# Sheet1.net
KiCad netlist of a schematic drawn in Altium Designer
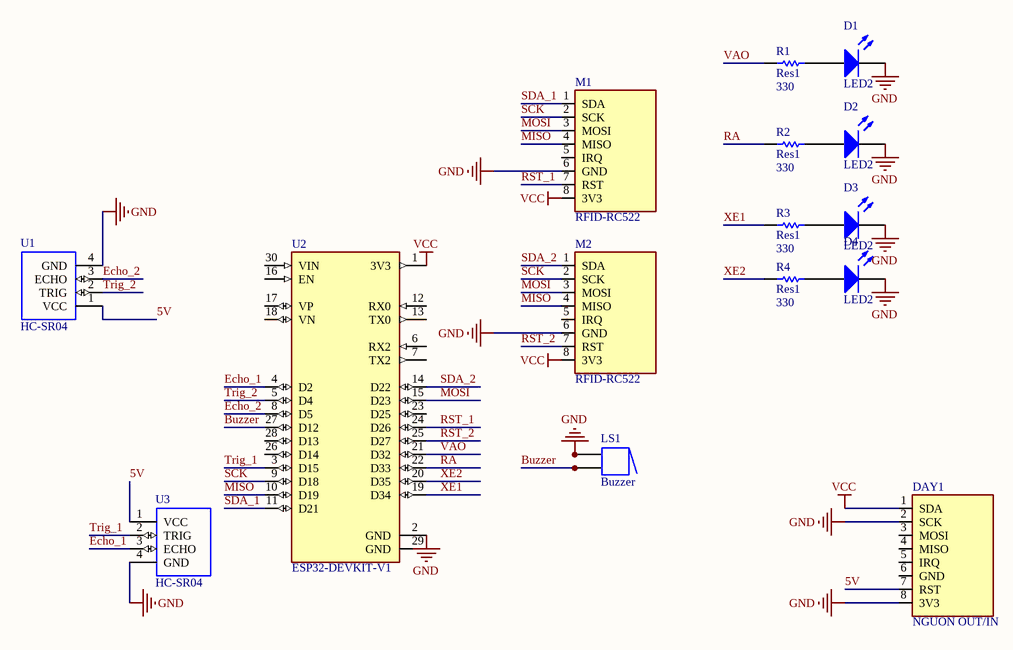
[diagram p0: Sheet1.SchDoc]

(export (version "E")
  (design (tool "Eeschema 10.0.6"))
  (components
    (comp (ref "D1")
      (value "LED2")
      (footprint "3.2X1.6X1.1")
      (description "Typical RED, GREEN, YELLOW, AMBER GaAs LED")
      (fields (field (name "PUBLISHER") "Altium Limited"))
      (libsource (lib "Miscellaneous Devices") (part "LED2"))
    )
    (comp (ref "D2")
      (value "LED2")
      (footprint "3.2X1.6X1.1")
      (description "Typical RED, GREEN, YELLOW, AMBER GaAs LED")
      (fields (field (name "PUBLISHER") "Altium Limited"))
      (libsource (lib "Miscellaneous Devices") (part "LED2"))
    )
    (comp (ref "D3")
      (value "LED2")
      (footprint "3.2X1.6X1.1")
      (description "Typical RED, GREEN, YELLOW, AMBER GaAs LED")
      (fields (field (name "PUBLISHER") "Altium Limited"))
      (libsource (lib "Miscellaneous Devices") (part "LED2"))
    )
    (comp (ref "D4")
      (value "LED2")
      (footprint "3.2X1.6X1.1")
      (description "Typical RED, GREEN, YELLOW, AMBER GaAs LED")
      (fields (field (name "PUBLISHER") "Altium Limited"))
      (libsource (lib "Miscellaneous Devices") (part "LED2"))
    )
    (comp (ref "DAY1")
      (value "NGUON OUT/IN")
      (footprint "RFID-RC522")
      (fields (field (name "MF") "Handson Technology") (field (name "MP") "RFID-RC522"))
      (libsource (lib "RFID-RC522") (part "RFID-RC522"))
    )
    (comp (ref "LS1")
      (value "Buzzer")
      (footprint "ABSM-1574")
      (description "Magnetic Transducer Buzzer")
      (fields (field (name "PUBLISHER") "Altium Limited"))
      (libsource (lib "Miscellaneous Devices") (part "Buzzer"))
    )
    (comp (ref "M1")
      (value "RFID-RC522")
      (footprint "RFID-RC522")
      (fields (field (name "MF") "Handson Technology"))
      (libsource (lib "RFID-RC522") (part "RFID-RC522"))
    )
    (comp (ref "M2")
      (value "RFID-RC522")
      (footprint "RFID-RC522")
      (fields (field (name "MF") "Handson Technology"))
      (libsource (lib "RFID-RC522") (part "RFID-RC522"))
    )
    (comp (ref "R1")
      (value "Res1")
      (footprint "AXIAL-0.3")
      (description "Resistor")
      (fields (field (name "ALTIUM_VALUE") "330") (field (name "PUBLISHER") "Altium Limited"))
      (libsource (lib "Miscellaneous Devices") (part "Res1"))
    )
    (comp (ref "R2")
      (value "Res1")
      (footprint "AXIAL-0.3")
      (description "Resistor")
      (fields (field (name "ALTIUM_VALUE") "330") (field (name "PUBLISHER") "Altium Limited"))
      (libsource (lib "Miscellaneous Devices") (part "Res1"))
    )
    (comp (ref "R3")
      (value "Res1")
      (footprint "AXIAL-0.3")
      (description "Resistor")
      (fields (field (name "ALTIUM_VALUE") "330") (field (name "PUBLISHER") "Altium Limited"))
      (libsource (lib "Miscellaneous Devices") (part "Res1"))
    )
    (comp (ref "R4")
      (value "Res1")
      (footprint "AXIAL-0.3")
      (description "Resistor")
      (fields (field (name "ALTIUM_VALUE") "330") (field (name "PUBLISHER") "Altium Limited"))
      (libsource (lib "Miscellaneous Devices") (part "Res1"))
    )
    (comp (ref "U1")
      (value "HC-SR04")
      (footprint "XCVR_HC-SR04")
      (description "Ultrasonic Sensor Module")
      (libsource (lib "HC-SR04") (part "HC-SR04"))
    )
    (comp (ref "U2")
      (value "ESP32-DEVKIT-V1")
      (footprint "MODULE_ESP32_DEVKIT_V1")
      (fields (field (name "MF") "Do it"))
      (libsource (lib "ESP32-DEVKIT-V1") (part "ESP32-DEVKIT-V1"))
    )
    (comp (ref "U3")
      (value "HC-SR04")
      (footprint "XCVR_HC-SR04")
      (description "Ultrasonic Sensor Module")
      (libsource (lib "HC-SR04") (part "HC-SR04"))
    )
  )
  (nets
    (net (code "1") (name "/5V") (class "Default")
      (node (ref "DAY1") (pin "7") (pinfunction "RST_7") (pintype "bidirectional"))
      (node (ref "U1") (pin "1") (pinfunction "VCC_1") (pintype "power_in"))
      (node (ref "U3") (pin "1") (pinfunction "VCC_1") (pintype "power_in"))
    )
    (net (code "2") (name "/Buzzer") (class "Default")
      (node (ref "LS1") (pin "2") (pinfunction "2_2") (pintype "passive"))
      (node (ref "LS1") (pin "2A") (pinfunction "2A_2A") (pintype "passive"))
      (node (ref "U2") (pin "27") (pinfunction "D12_27") (pintype "bidirectional"))
    )
    (net (code "3") (name "/Echo_1") (class "Default")
      (node (ref "U2") (pin "4") (pinfunction "D2_4") (pintype "bidirectional"))
      (node (ref "U3") (pin "3") (pinfunction "ECHO_3") (pintype "bidirectional"))
    )
    (net (code "4") (name "/Echo_2") (class "Default")
      (node (ref "U1") (pin "3") (pinfunction "ECHO_3") (pintype "bidirectional"))
      (node (ref "U2") (pin "8") (pinfunction "D5_8") (pintype "bidirectional"))
    )
    (net (code "5") (name "/MISO") (class "Default")
      (node (ref "M1") (pin "4") (pinfunction "MISO_4") (pintype "bidirectional"))
      (node (ref "M2") (pin "4") (pinfunction "MISO_4") (pintype "bidirectional"))
      (node (ref "U2") (pin "10") (pinfunction "D19_10") (pintype "bidirectional"))
    )
    (net (code "6") (name "/MOSI") (class "Default")
      (node (ref "M1") (pin "3") (pinfunction "MOSI_3") (pintype "bidirectional"))
      (node (ref "M2") (pin "3") (pinfunction "MOSI_3") (pintype "bidirectional"))
      (node (ref "U2") (pin "15") (pinfunction "D23_15") (pintype "bidirectional"))
    )
    (net (code "7") (name "/RA") (class "Default")
      (node (ref "R2") (pin "1") (pinfunction "1_1") (pintype "passive"))
      (node (ref "U2") (pin "22") (pinfunction "D33_22") (pintype "bidirectional"))
    )
    (net (code "8") (name "/RST_1") (class "Default")
      (node (ref "M1") (pin "7") (pinfunction "RST_7") (pintype "bidirectional"))
      (node (ref "U2") (pin "24") (pinfunction "D26_24") (pintype "bidirectional"))
    )
    (net (code "9") (name "/RST_2") (class "Default")
      (node (ref "M2") (pin "7") (pinfunction "RST_7") (pintype "bidirectional"))
      (node (ref "U2") (pin "25") (pinfunction "D27_25") (pintype "bidirectional"))
    )
    (net (code "10") (name "/SCK") (class "Default")
      (node (ref "M1") (pin "2") (pinfunction "SCK_2") (pintype "bidirectional"))
      (node (ref "M2") (pin "2") (pinfunction "SCK_2") (pintype "bidirectional"))
      (node (ref "U2") (pin "9") (pinfunction "D18_9") (pintype "bidirectional"))
    )
    (net (code "11") (name "/SDA_1") (class "Default")
      (node (ref "M1") (pin "1") (pinfunction "SDA_1") (pintype "bidirectional"))
      (node (ref "U2") (pin "11") (pinfunction "D21_11") (pintype "bidirectional"))
    )
    (net (code "12") (name "/SDA_2") (class "Default")
      (node (ref "M2") (pin "1") (pinfunction "SDA_1") (pintype "bidirectional"))
      (node (ref "U2") (pin "14") (pinfunction "D22_14") (pintype "bidirectional"))
    )
    (net (code "13") (name "/Trig_1") (class "Default")
      (node (ref "U2") (pin "3") (pinfunction "D15_3") (pintype "bidirectional"))
      (node (ref "U3") (pin "2") (pinfunction "TRIG_2") (pintype "bidirectional"))
    )
    (net (code "14") (name "/Trig_2") (class "Default")
      (node (ref "U1") (pin "2") (pinfunction "TRIG_2") (pintype "bidirectional"))
      (node (ref "U2") (pin "5") (pinfunction "D4_5") (pintype "bidirectional"))
    )
    (net (code "15") (name "/VAO") (class "Default")
      (node (ref "R1") (pin "1") (pinfunction "1_1") (pintype "passive"))
      (node (ref "U2") (pin "21") (pinfunction "D32_21") (pintype "bidirectional"))
    )
    (net (code "16") (name "/XE1") (class "Default")
      (node (ref "R3") (pin "1") (pinfunction "1_1") (pintype "passive"))
      (node (ref "U2") (pin "19") (pinfunction "D34_19") (pintype "bidirectional"))
    )
    (net (code "17") (name "/XE2") (class "Default")
      (node (ref "R4") (pin "1") (pinfunction "1_1") (pintype "passive"))
      (node (ref "U2") (pin "20") (pinfunction "D35_20") (pintype "bidirectional"))
    )
    (net (code "18") (name "GND") (class "Default")
      (node (ref "D1") (pin "2") (pinfunction "K_2") (pintype "passive"))
      (node (ref "D2") (pin "2") (pinfunction "K_2") (pintype "passive"))
      (node (ref "D3") (pin "2") (pinfunction "K_2") (pintype "passive"))
      (node (ref "D4") (pin "2") (pinfunction "K_2") (pintype "passive"))
      (node (ref "DAY1") (pin "2") (pinfunction "SCK_2") (pintype "bidirectional"))
      (node (ref "DAY1") (pin "8") (pinfunction "3V3_8") (pintype "bidirectional"))
      (node (ref "LS1") (pin "1") (pinfunction "1_1") (pintype "passive"))
      (node (ref "LS1") (pin "1A") (pinfunction "1A_1A") (pintype "passive"))
      (node (ref "M1") (pin "6") (pinfunction "GND_6") (pintype "bidirectional"))
      (node (ref "M2") (pin "6") (pinfunction "GND_6") (pintype "bidirectional"))
      (node (ref "U1") (pin "4") (pinfunction "GND_4") (pintype "power_in"))
      (node (ref "U2") (pin "2") (pinfunction "GND_2") (pintype "power_in"))
      (node (ref "U3") (pin "4") (pinfunction "GND_4") (pintype "power_in"))
    )
    (net (code "19") (name "Net-(D1-A)") (class "Default")
      (node (ref "D1") (pin "1") (pinfunction "A_1") (pintype "passive"))
      (node (ref "R1") (pin "2") (pinfunction "2_2") (pintype "passive"))
    )
    (net (code "20") (name "Net-(D2-A)") (class "Default")
      (node (ref "D2") (pin "1") (pinfunction "A_1") (pintype "passive"))
      (node (ref "R2") (pin "2") (pinfunction "2_2") (pintype "passive"))
    )
    (net (code "21") (name "Net-(D3-A)") (class "Default")
      (node (ref "D3") (pin "1") (pinfunction "A_1") (pintype "passive"))
      (node (ref "R3") (pin "2") (pinfunction "2_2") (pintype "passive"))
    )
    (net (code "22") (name "Net-(D4-A)") (class "Default")
      (node (ref "D4") (pin "1") (pinfunction "A_1") (pintype "passive"))
      (node (ref "R4") (pin "2") (pinfunction "2_2") (pintype "passive"))
    )
    (net (code "23") (name "VCC") (class "Default")
      (node (ref "DAY1") (pin "1") (pinfunction "SDA_1") (pintype "bidirectional"))
      (node (ref "M1") (pin "8") (pinfunction "3V3_8") (pintype "bidirectional"))
      (node (ref "M2") (pin "8") (pinfunction "3V3_8") (pintype "bidirectional"))
      (node (ref "U2") (pin "1") (pinfunction "3V3_1") (pintype "output"))
    )
    (net (code "24") (name "unconnected-(DAY1-GND-Pad6)") (class "Default")
      (node (ref "DAY1") (pin "6") (pinfunction "GND_6") (pintype "bidirectional"))
    )
    (net (code "25") (name "unconnected-(DAY1-IRQ-Pad5)") (class "Default")
      (node (ref "DAY1") (pin "5") (pinfunction "IRQ_5") (pintype "bidirectional"))
    )
    (net (code "26") (name "unconnected-(DAY1-MISO-Pad4)") (class "Default")
      (node (ref "DAY1") (pin "4") (pinfunction "MISO_4") (pintype "bidirectional"))
    )
    (net (code "27") (name "unconnected-(DAY1-MOSI-Pad3)") (class "Default")
      (node (ref "DAY1") (pin "3") (pinfunction "MOSI_3") (pintype "bidirectional"))
    )
    (net (code "28") (name "unconnected-(M1-IRQ-Pad5)") (class "Default")
      (node (ref "M1") (pin "5") (pinfunction "IRQ_5") (pintype "bidirectional"))
    )
    (net (code "29") (name "unconnected-(M2-IRQ-Pad5)") (class "Default")
      (node (ref "M2") (pin "5") (pinfunction "IRQ_5") (pintype "bidirectional"))
    )
    (net (code "30") (name "unconnected-(U2-D13-Pad28)") (class "Default")
      (node (ref "U2") (pin "28") (pinfunction "D13_28") (pintype "bidirectional"))
    )
    (net (code "31") (name "unconnected-(U2-D14-Pad26)") (class "Default")
      (node (ref "U2") (pin "26") (pinfunction "D14_26") (pintype "bidirectional"))
    )
    (net (code "32") (name "unconnected-(U2-D25-Pad23)") (class "Default")
      (node (ref "U2") (pin "23") (pinfunction "D25_23") (pintype "bidirectional"))
    )
    (net (code "33") (name "unconnected-(U2-EN-Pad16)") (class "Default")
      (node (ref "U2") (pin "16") (pinfunction "EN_16") (pintype "input"))
    )
    (net (code "34") (name "unconnected-(U2-GND-Pad29)") (class "Default")
      (node (ref "U2") (pin "29") (pinfunction "GND_29") (pintype "power_in"))
    )
    (net (code "35") (name "unconnected-(U2-RX0-Pad12)") (class "Default")
      (node (ref "U2") (pin "12") (pinfunction "RX0_12") (pintype "input"))
    )
    (net (code "36") (name "unconnected-(U2-RX2-Pad6)") (class "Default")
      (node (ref "U2") (pin "6") (pinfunction "RX2_6") (pintype "input"))
    )
    (net (code "37") (name "unconnected-(U2-TX0-Pad13)") (class "Default")
      (node (ref "U2") (pin "13") (pinfunction "TX0_13") (pintype "output"))
    )
    (net (code "38") (name "unconnected-(U2-TX2-Pad7)") (class "Default")
      (node (ref "U2") (pin "7") (pinfunction "TX2_7") (pintype "output"))
    )
    (net (code "39") (name "unconnected-(U2-VIN-Pad30)") (class "Default")
      (node (ref "U2") (pin "30") (pinfunction "VIN_30") (pintype "input"))
    )
    (net (code "40") (name "unconnected-(U2-VN-Pad18)") (class "Default")
      (node (ref "U2") (pin "18") (pinfunction "VN_18") (pintype "bidirectional"))
    )
    (net (code "41") (name "unconnected-(U2-VP-Pad17)") (class "Default")
      (node (ref "U2") (pin "17") (pinfunction "VP_17") (pintype "bidirectional"))
    )
  )
)
